# STM32F405RGT6.net
KiCad netlist of a schematic drawn in Altium Designer
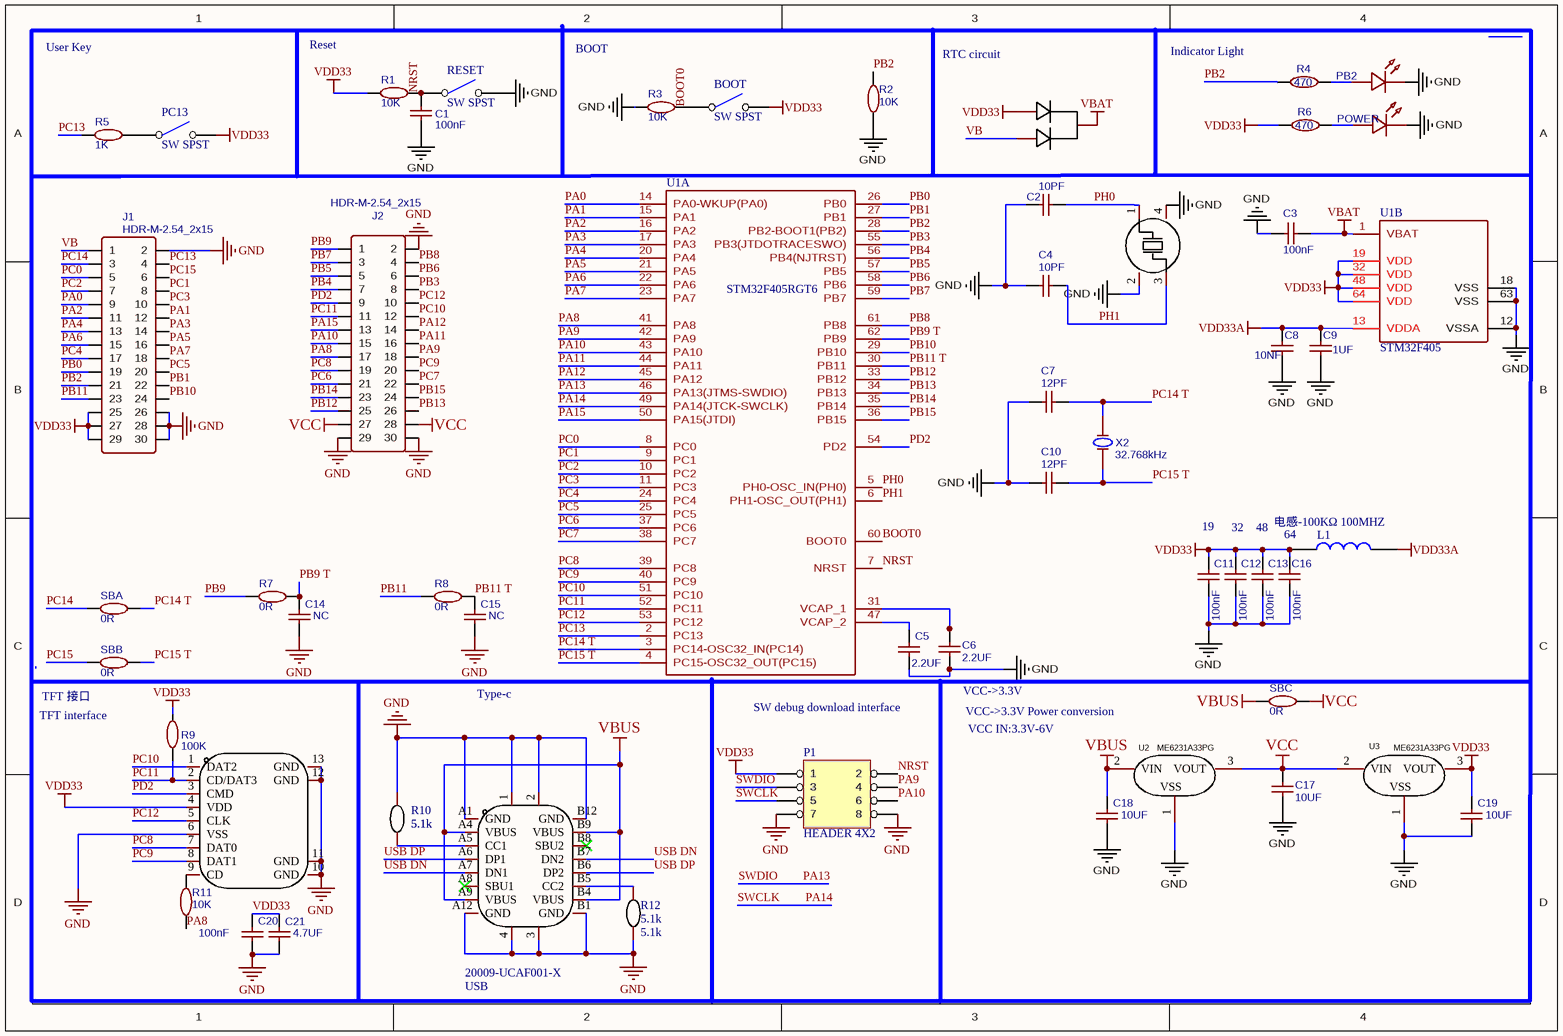
[diagram p0: STM32F405RGT6 .schdoc]

(export (version "E")
  (design (tool "Eeschema 10.0.6"))
  (components
    (comp (ref "BOOT") (value "SW SPST") (footprint "KEY-SMD1") (libsource (lib "杂元件库") (part "SW SPST")))
    (comp (ref "C1")
      (value "100nF")
      (footprint "C0603")
      (fields (field (name "MANUFACTURER") "FH") (field (name "MANUFACTURER PART") "0603B104K500NT"))
      (libsource (lib "altium-import") (part "root_1_100nF_"))
    )
    (comp (ref "C2")
      (value "10PF")
      (footprint "C0603")
      (fields (field (name "MANUFACTURER") "YAGEO") (field (name "MANUFACTURER PART") "CC0603JRNPO9BN200"))
      (libsource (lib "altium-import") (part "root_0_20pF_"))
    )
    (comp (ref "C3")
      (value "100nF")
      (footprint "C0603")
      (fields (field (name "MANUFACTURER") "FH") (field (name "MANUFACTURER PART") "0603B104K500NT"))
      (libsource (lib "altium-import") (part "root_2_100nF_"))
    )
    (comp (ref "C4")
      (value "10PF")
      (footprint "C0603")
      (fields (field (name "MANUFACTURER") "YAGEO") (field (name "MANUFACTURER PART") "CC0603JRNPO9BN200"))
      (libsource (lib "altium-import") (part "root_0_20pF_"))
    )
    (comp (ref "C5")
      (value "2.2UF")
      (footprint "C0603")
      (fields (field (name "MANUFACTURER") "FH") (field (name "MANUFACTURER PART") "0603B104K500NT"))
      (libsource (lib "altium-import") (part "root_1_100nF_"))
    )
    (comp (ref "C6")
      (value "2.2UF")
      (footprint "C0603")
      (fields (field (name "MANUFACTURER") "FH") (field (name "MANUFACTURER PART") "0603B104K500NT"))
      (libsource (lib "altium-import") (part "root_1_100nF_"))
    )
    (comp (ref "C7")
      (value "12PF")
      (footprint "C0603")
      (fields (field (name "MANUFACTURER") "YAGEO") (field (name "MANUFACTURER PART") "CC0603JRNPO9BN200"))
      (libsource (lib "altium-import") (part "root_0_20pF_"))
    )
    (comp (ref "C8")
      (value "10NF")
      (footprint "C0603")
      (fields (field (name "MANUFACTURER") "FH") (field (name "MANUFACTURER PART") "0603B104K500NT"))
      (libsource (lib "altium-import") (part "root_1_100nF_"))
    )
    (comp (ref "C9")
      (value "1UF")
      (footprint "C0603")
      (fields (field (name "MANUFACTURER") "FH") (field (name "MANUFACTURER PART") "0603B104K500NT"))
      (libsource (lib "altium-import") (part "root_1_100nF_"))
    )
    (comp (ref "C10")
      (value "12PF")
      (footprint "C0603")
      (fields (field (name "MANUFACTURER") "YAGEO") (field (name "MANUFACTURER PART") "CC0603JRNPO9BN200"))
      (libsource (lib "altium-import") (part "root_0_20pF_"))
    )
    (comp (ref "C11")
      (value "100nF")
      (footprint "C0603")
      (fields (field (name "MANUFACTURER") "FH") (field (name "MANUFACTURER PART") "0603B104K500NT"))
      (libsource (lib "altium-import") (part "root_1_100nF_"))
    )
    (comp (ref "C12")
      (value "100nF")
      (footprint "C0603")
      (fields (field (name "MANUFACTURER") "FH") (field (name "MANUFACTURER PART") "0603B104K500NT"))
      (libsource (lib "altium-import") (part "root_1_100nF_"))
    )
    (comp (ref "C13")
      (value "100nF")
      (footprint "C0603")
      (fields (field (name "MANUFACTURER") "FH") (field (name "MANUFACTURER PART") "0603B104K500NT"))
      (libsource (lib "altium-import") (part "root_1_100nF_"))
    )
    (comp (ref "C14")
      (value "NC")
      (footprint "C0603")
      (fields (field (name "MANUFACTURER") "FH") (field (name "MANUFACTURER PART") "0603B104K500NT"))
      (libsource (lib "altium-import") (part "root_1_100nF_"))
    )
    (comp (ref "C15")
      (value "NC")
      (footprint "C0603")
      (fields (field (name "MANUFACTURER") "FH") (field (name "MANUFACTURER PART") "0603B104K500NT"))
      (libsource (lib "altium-import") (part "root_1_100nF_"))
    )
    (comp (ref "C16")
      (value "100nF")
      (footprint "C0603")
      (fields (field (name "MANUFACTURER") "FH") (field (name "MANUFACTURER PART") "0603B104K500NT"))
      (libsource (lib "altium-import") (part "root_1_100nF_"))
    )
    (comp (ref "C17")
      (value "10UF")
      (footprint "C0603")
      (fields (field (name "MANUFACTURER") "FH") (field (name "MANUFACTURER PART") "0603B104K500NT"))
      (libsource (lib "altium-import") (part "root_3_100nF_"))
    )
    (comp (ref "C18")
      (value "10UF")
      (footprint "C0603")
      (fields (field (name "MANUFACTURER") "FH") (field (name "MANUFACTURER PART") "0603B104K500NT"))
      (libsource (lib "altium-import") (part "root_1_100nF_"))
    )
    (comp (ref "C19")
      (value "10UF")
      (footprint "C0603")
      (fields (field (name "MANUFACTURER") "FH") (field (name "MANUFACTURER PART") "0603B104K500NT"))
      (libsource (lib "altium-import") (part "root_1_100nF_"))
    )
    (comp (ref "C20")
      (value "100nF")
      (footprint "C0603")
      (fields (field (name "MANUFACTURER") "FH") (field (name "MANUFACTURER PART") "0603B104K500NT"))
      (libsource (lib "altium-import") (part "root_1_100nF_"))
    )
    (comp (ref "C21")
      (value "4.7UF")
      (footprint "C0603")
      (fields (field (name "MANUFACTURER") "FH") (field (name "MANUFACTURER PART") "0603B104K500NT"))
      (libsource (lib "altium-import") (part "root_1_100nF_"))
    )
    (comp (ref "CARD1")
      (value "TF-01A")
      (footprint "SD -TF-01A")
      (fields (field (name "MANUFACTURER") "Yuandi(元迪)"))
      (libsource (lib "altium-import") (part "root_0_TF-01A_C2889258_"))
    )
    (comp (ref "D1")
      (value "BAT54C")
      (footprint "SOT-23")
      (fields (field (name "MANUFACTURER") "CJ(江苏长电/长晶)"))
      (libsource (lib "altium-import") (part "root_0_BAT54C_C2135_"))
    )
    (comp (ref "J1")
      (value "HDR-M-2.54_2x15")
      (footprint "HDR2X15-")
      (fields (field (name "CONTRIBUTOR") "LCEDA_Lib"))
      (libsource (lib "altium-import") (part "root_0_HDR-M-2.54_2x15_"))
    )
    (comp (ref "J2")
      (value "HDR-M-2.54_2x15")
      (footprint "HDR2X15-")
      (fields (field (name "CONTRIBUTOR") "LCEDA_Lib"))
      (libsource (lib "altium-import") (part "root_0_HDR-M-2.54_2x15_"))
    )
    (comp (ref "L1") (value "电感-100KΩ 100MHZ") (footprint "L0603") (libsource (lib "杂元件库") (part "电感")))
    (comp (ref "P1")
      (value "HEADER 4X2")
      (footprint "HDR2X4H-OK")
      (libsource (lib "杂元件库") (part "HEADER 4X2"))
    )
    (comp (ref "PB2")
      (value "LED-0603_G")
      (footprint "LED0603-G")
      (fields
        (field (name "MANUFACTURER") "EVERLIGHT(台湾亿光)")
        (field (name "MANUFACTURER PART") "19-217/R6C-AL1M2VY/3T")
        (field (name "CONTRIBUTOR") "LCEDA_01")
      )
      (libsource (lib "altium-import") (part "root_0_LED-0603_R_"))
    )
    (comp (ref "PC13") (value "SW SPST") (footprint "KEY-SMD1") (libsource (lib "杂元件库") (part "SW SPST")))
    (comp (ref "POWER")
      (value "LED-0603_R")
      (footprint "LED0603-R")
      (fields
        (field (name "MANUFACTURER") "EVERLIGHT(台湾亿光)")
        (field (name "MANUFACTURER PART") "19-217/R6C-AL1M2VY/3T")
        (field (name "CONTRIBUTOR") "LCEDA_01")
      )
      (libsource (lib "altium-import") (part "root_0_LED-0603_R_"))
    )
    (comp (ref "R1")
      (value "10K")
      (footprint "R0603")
      (fields (field (name "MANUFACTURER") "YAGEO") (field (name "MANUFACTURER PART") "RC0603FR-0710KL"))
      (libsource (lib "altium-import") (part "root_2_10K_"))
    )
    (comp (ref "R2")
      (value "10K")
      (footprint "R0603")
      (fields (field (name "MANUFACTURER") "YAGEO") (field (name "MANUFACTURER PART") "RC0603FR-0710KL"))
      (libsource (lib "altium-import") (part "root_3_10K_"))
    )
    (comp (ref "R3")
      (value "10K")
      (footprint "R0603")
      (fields (field (name "MANUFACTURER") "YAGEO") (field (name "MANUFACTURER PART") "RC0603FR-0710KL"))
      (libsource (lib "altium-import") (part "root_2_10K_"))
    )
    (comp (ref "R4")
      (value "470")
      (footprint "R0603")
      (fields (field (name "MANUFACTURER") "UniOhm") (field (name "MANUFACTURER PART") "0603WAJ0471T5E"))
      (libsource (lib "altium-import") (part "root_0_470_"))
    )
    (comp (ref "R5")
      (value "1K")
      (footprint "R0603")
      (fields (field (name "MANUFACTURER") "YAGEO") (field (name "MANUFACTURER PART") "RC0603FR-0710KL"))
      (libsource (lib "altium-import") (part "root_2_10K_"))
    )
    (comp (ref "R6")
      (value "470")
      (footprint "R0603")
      (fields (field (name "MANUFACTURER") "UniOhm") (field (name "MANUFACTURER PART") "0603WAJ0471T5E"))
      (libsource (lib "altium-import") (part "root_0_470_"))
    )
    (comp (ref "R7")
      (value "0R")
      (footprint "R0603")
      (fields (field (name "MANUFACTURER") "YAGEO") (field (name "MANUFACTURER PART") "RC0603FR-0710KL"))
      (libsource (lib "altium-import") (part "root_2_10K_"))
    )
    (comp (ref "R8")
      (value "0R")
      (footprint "R0603")
      (fields (field (name "MANUFACTURER") "YAGEO") (field (name "MANUFACTURER PART") "RC0603FR-0710KL"))
      (libsource (lib "altium-import") (part "root_2_10K_"))
    )
    (comp (ref "R9")
      (value "100K")
      (footprint "R0603")
      (fields (field (name "MANUFACTURER") "YAGEO") (field (name "MANUFACTURER PART") "RC0603FR-0710KL"))
      (libsource (lib "altium-import") (part "root_1_10K_"))
    )
    (comp (ref "R10")
      (value "5.1k")
      (footprint "R0603")
      (fields (field (name "NAME") "5.1k"))
      (libsource (lib "altium-import") (part "root_1_5.1k_"))
    )
    (comp (ref "R11")
      (value "10K")
      (footprint "R0603")
      (fields (field (name "MANUFACTURER") "YAGEO") (field (name "MANUFACTURER PART") "RC0603FR-0710KL"))
      (libsource (lib "altium-import") (part "root_3_10K_"))
    )
    (comp (ref "R12")
      (value "5.1k")
      (footprint "R0603")
      (fields (field (name "NAME") "5.1k"))
      (libsource (lib "altium-import") (part "root_3_5.1k_"))
    )
    (comp (ref "RESET") (value "SW SPST") (footprint "KEY-SMD1") (libsource (lib "杂元件库") (part "SW SPST")))
    (comp (ref "SBA")
      (value "0R")
      (footprint "R0805")
      (fields (field (name "MANUFACTURER") "YAGEO") (field (name "MANUFACTURER PART") "RC0603FR-0710KL"))
      (libsource (lib "altium-import") (part "root_2_10K_"))
    )
    (comp (ref "SBB")
      (value "0R")
      (footprint "R0805")
      (fields (field (name "MANUFACTURER") "YAGEO") (field (name "MANUFACTURER PART") "RC0603FR-0710KL"))
      (libsource (lib "altium-import") (part "root_2_10K_"))
    )
    (comp (ref "SBC")
      (value "0R")
      (footprint "R0805")
      (fields (field (name "MANUFACTURER") "YAGEO") (field (name "MANUFACTURER PART") "RC0603FR-0710KL"))
      (libsource (lib "altium-import") (part "root_2_10K_"))
    )
    (comp (ref "U1") (value "STM32F405RGT6") (footprint "QFP-64") (libsource (lib "杂元件库") (part "STM32F405")))
    (comp (ref "U2")
      (value "ME6231A33PG")
      (footprint "SOT-89")
      (fields (field (name "MANUFACTURER") "MICRONE(南京微盟)"))
      (libsource (lib "altium-import") (part "root_0_ME6231A33PG_"))
    )
    (comp (ref "U3")
      (value "ME6231A33PG")
      (footprint "SOT-89")
      (fields (field (name "MANUFACTURER") "MICRONE(南京微盟)"))
      (libsource (lib "altium-import") (part "root_0_ME6231A33PG_"))
    )
    (comp (ref "USB")
      (value "20009-UCAF001-X")
      (footprint "TYPE-C-16P")
      (fields (field (name "NAME") "20009-UCAF001-X") (field (name "MANUFACTURER") "MINTRON(��˶)"))
      (libsource (lib "altium-import") (part "root_0_20009-UCAF001-X_"))
    )
    (comp (ref "X1")
      (value "8MHz")
      (footprint "3225晶振")
      (description "C20617566")
      (fields (field (name "MANUFACTURER") "YXC(扬兴晶振)") (field (name "MANUFACTURER PART") "X322525MOB4SI"))
      (libsource (lib "altium-import") (part "root_3_X322525MOB4SI_"))
    )
    (comp (ref "X2")
      (value "32.768kHz")
      (footprint "3215")
      (fields (field (name "MANUFACTURER PART") "X308032768KGB2SC") (field (name "MANUFACTURER") "YXC(扬兴晶振)"))
      (libsource (lib "altium-import") (part "root_1_32.768kHz_"))
    )
  )
  (nets
    (net (code "1") (name "/BOOT0") (class "Default")
      (node (ref "BOOT") (pin "1") (pinfunction "COMMON_1") (pintype "passive"))
      (node (ref "R3") (pin "1") (pinfunction "1_1") (pintype "passive"))
      (node (ref "U1") (pin "60") (pinfunction "BOOT0_60") (pintype "passive"))
    )
    (net (code "2") (name "/NRST") (class "Default")
      (node (ref "C1") (pin "2") (pinfunction "2_2") (pintype "passive"))
      (node (ref "P1") (pin "2") (pinfunction "2_2") (pintype "passive"))
      (node (ref "R1") (pin "1") (pinfunction "1_1") (pintype "passive"))
      (node (ref "RESET") (pin "1") (pinfunction "COMMON_1") (pintype "passive"))
      (node (ref "U1") (pin "7") (pinfunction "NRST_7") (pintype "passive"))
    )
    (net (code "3") (name "/PA0") (class "Default")
      (node (ref "J1") (pin "9") (pinfunction "9_9") (pintype "passive"))
      (node (ref "U1") (pin "14") (pinfunction "PA0-WKUP(PA0)_14") (pintype "passive"))
    )
    (net (code "4") (name "/PA1") (class "Default")
      (node (ref "J1") (pin "12") (pinfunction "12_12") (pintype "passive"))
      (node (ref "U1") (pin "15") (pinfunction "PA1_15") (pintype "passive"))
    )
    (net (code "5") (name "/PA2") (class "Default")
      (node (ref "J1") (pin "11") (pinfunction "11_11") (pintype "passive"))
      (node (ref "U1") (pin "16") (pinfunction "PA2_16") (pintype "passive"))
    )
    (net (code "6") (name "/PA3") (class "Default")
      (node (ref "J1") (pin "14") (pinfunction "14_14") (pintype "passive"))
      (node (ref "U1") (pin "17") (pinfunction "PA3_17") (pintype "passive"))
    )
    (net (code "7") (name "/PA4") (class "Default")
      (node (ref "J1") (pin "13") (pinfunction "13_13") (pintype "passive"))
      (node (ref "U1") (pin "20") (pinfunction "PA4_20") (pintype "passive"))
    )
    (net (code "8") (name "/PA5") (class "Default")
      (node (ref "J1") (pin "16") (pinfunction "16_16") (pintype "passive"))
      (node (ref "U1") (pin "21") (pinfunction "PA5_21") (pintype "passive"))
    )
    (net (code "9") (name "/PA6") (class "Default")
      (node (ref "J1") (pin "15") (pinfunction "15_15") (pintype "passive"))
      (node (ref "U1") (pin "22") (pinfunction "PA6_22") (pintype "passive"))
    )
    (net (code "10") (name "/PA7") (class "Default")
      (node (ref "J1") (pin "18") (pinfunction "18_18") (pintype "passive"))
      (node (ref "U1") (pin "23") (pinfunction "PA7_23") (pintype "passive"))
    )
    (net (code "11") (name "/PA8") (class "Default")
      (node (ref "J2") (pin "17") (pinfunction "17_17") (pintype "passive"))
      (node (ref "R11") (pin "2") (pinfunction "2_2") (pintype "passive"))
      (node (ref "U1") (pin "41") (pinfunction "PA8_41") (pintype "passive"))
    )
    (net (code "12") (name "/PA9") (class "Default")
      (node (ref "J2") (pin "18") (pinfunction "18_18") (pintype "passive"))
      (node (ref "P1") (pin "4") (pinfunction "4_4") (pintype "passive"))
      (node (ref "U1") (pin "42") (pinfunction "PA9_42") (pintype "passive"))
    )
    (net (code "13") (name "/PA10") (class "Default")
      (node (ref "J2") (pin "15") (pinfunction "15_15") (pintype "passive"))
      (node (ref "P1") (pin "6") (pinfunction "6_6") (pintype "passive"))
      (node (ref "U1") (pin "43") (pinfunction "PA10_43") (pintype "passive"))
    )
    (net (code "14") (name "/PA11") (class "Default")
      (node (ref "J2") (pin "16") (pinfunction "16_16") (pintype "passive"))
      (node (ref "U1") (pin "44") (pinfunction "PA11_44") (pintype "passive"))
    )
    (net (code "15") (name "/PA12") (class "Default")
      (node (ref "J2") (pin "14") (pinfunction "14_14") (pintype "passive"))
      (node (ref "U1") (pin "45") (pinfunction "PA12_45") (pintype "passive"))
    )
    (net (code "16") (name "/PA13") (class "Default")
      (node (ref "P1") (pin "3") (pinfunction "3_3") (pintype "passive"))
      (node (ref "U1") (pin "46") (pinfunction "PA13(JTMS-SWDIO)_46") (pintype "passive"))
    )
    (net (code "17") (name "/PA14") (class "Default")
      (node (ref "P1") (pin "5") (pinfunction "5_5") (pintype "passive"))
      (node (ref "U1") (pin "49") (pinfunction "PA14(JTCK-SWCLK)_49") (pintype "passive"))
    )
    (net (code "18") (name "/PA15") (class "Default")
      (node (ref "J2") (pin "13") (pinfunction "13_13") (pintype "passive"))
      (node (ref "U1") (pin "50") (pinfunction "PA15(JTDI)_50") (pintype "passive"))
    )
    (net (code "19") (name "/PB0") (class "Default")
      (node (ref "J1") (pin "19") (pinfunction "19_19") (pintype "passive"))
      (node (ref "U1") (pin "26") (pinfunction "PB0_26") (pintype "passive"))
    )
    (net (code "20") (name "/PB1") (class "Default")
      (node (ref "J1") (pin "22") (pinfunction "22_22") (pintype "passive"))
      (node (ref "U1") (pin "27") (pinfunction "PB1_27") (pintype "passive"))
    )
    (net (code "21") (name "/PB2") (class "Default")
      (node (ref "J1") (pin "21") (pinfunction "21_21") (pintype "passive"))
      (node (ref "R2") (pin "1") (pinfunction "1_1") (pintype "passive"))
      (node (ref "R4") (pin "1") (pinfunction "1_1") (pintype "passive"))
      (node (ref "U1") (pin "28") (pinfunction "PB2-BOOT1(PB2)_28") (pintype "passive"))
    )
    (net (code "22") (name "/PB3") (class "Default")
      (node (ref "J2") (pin "8") (pinfunction "8_8") (pintype "passive"))
      (node (ref "U1") (pin "55") (pinfunction "PB3(JTDOTRACESWO)_55") (pintype "passive"))
    )
    (net (code "23") (name "/PB4") (class "Default")
      (node (ref "J2") (pin "7") (pinfunction "7_7") (pintype "passive"))
      (node (ref "U1") (pin "56") (pinfunction "PB4(NJTRST)_56") (pintype "passive"))
    )
    (net (code "24") (name "/PB5") (class "Default")
      (node (ref "J2") (pin "5") (pinfunction "5_5") (pintype "passive"))
      (node (ref "U1") (pin "57") (pinfunction "PB5_57") (pintype "passive"))
    )
    (net (code "25") (name "/PB6") (class "Default")
      (node (ref "J2") (pin "6") (pinfunction "6_6") (pintype "passive"))
      (node (ref "U1") (pin "58") (pinfunction "PB6_58") (pintype "passive"))
    )
    (net (code "26") (name "/PB7") (class "Default")
      (node (ref "J2") (pin "3") (pinfunction "3_3") (pintype "passive"))
      (node (ref "U1") (pin "59") (pinfunction "PB7_59") (pintype "passive"))
    )
    (net (code "27") (name "/PB8") (class "Default")
      (node (ref "J2") (pin "4") (pinfunction "4_4") (pintype "passive"))
      (node (ref "U1") (pin "61") (pinfunction "PB8_61") (pintype "passive"))
    )
    (net (code "28") (name "/PB9") (class "Default")
      (node (ref "J2") (pin "1") (pinfunction "1_1") (pintype "passive"))
      (node (ref "R7") (pin "2") (pinfunction "2_2") (pintype "passive"))
    )
    (net (code "29") (name "/PB9 T") (class "Default")
      (node (ref "C14") (pin "2") (pinfunction "2_2") (pintype "passive"))
      (node (ref "R7") (pin "1") (pinfunction "1_1") (pintype "passive"))
      (node (ref "U1") (pin "62") (pinfunction "PB9_62") (pintype "passive"))
    )
    (net (code "30") (name "/PB10") (class "Default")
      (node (ref "J1") (pin "24") (pinfunction "24_24") (pintype "passive"))
      (node (ref "U1") (pin "29") (pinfunction "PB10_29") (pintype "passive"))
    )
    (net (code "31") (name "/PB11") (class "Default")
      (node (ref "J1") (pin "23") (pinfunction "23_23") (pintype "passive"))
      (node (ref "R8") (pin "2") (pinfunction "2_2") (pintype "passive"))
    )
    (net (code "32") (name "/PB11 T") (class "Default")
      (node (ref "C15") (pin "2") (pinfunction "2_2") (pintype "passive"))
      (node (ref "R8") (pin "1") (pinfunction "1_1") (pintype "passive"))
      (node (ref "U1") (pin "30") (pinfunction "PB11_30") (pintype "passive"))
    )
    (net (code "33") (name "/PB12") (class "Default")
      (node (ref "J2") (pin "25") (pinfunction "25_25") (pintype "passive"))
      (node (ref "U1") (pin "33") (pinfunction "PB12_33") (pintype "passive"))
    )
    (net (code "34") (name "/PB13") (class "Default")
      (node (ref "J2") (pin "26") (pinfunction "26_26") (pintype "passive"))
      (node (ref "U1") (pin "34") (pinfunction "PB13_34") (pintype "passive"))
    )
    (net (code "35") (name "/PB14") (class "Default")
      (node (ref "J2") (pin "23") (pinfunction "23_23") (pintype "passive"))
      (node (ref "U1") (pin "35") (pinfunction "PB14_35") (pintype "passive"))
    )
    (net (code "36") (name "/PB15") (class "Default")
      (node (ref "J2") (pin "24") (pinfunction "24_24") (pintype "passive"))
      (node (ref "U1") (pin "36") (pinfunction "PB15_36") (pintype "passive"))
    )
    (net (code "37") (name "/PC0") (class "Default")
      (node (ref "J1") (pin "5") (pinfunction "5_5") (pintype "passive"))
      (node (ref "U1") (pin "8") (pinfunction "PC0_8") (pintype "passive"))
    )
    (net (code "38") (name "/PC1") (class "Default")
      (node (ref "J1") (pin "8") (pinfunction "8_8") (pintype "passive"))
      (node (ref "U1") (pin "9") (pinfunction "PC1_9") (pintype "passive"))
    )
    (net (code "39") (name "/PC2") (class "Default")
      (node (ref "J1") (pin "7") (pinfunction "7_7") (pintype "passive"))
      (node (ref "U1") (pin "10") (pinfunction "PC2_10") (pintype "passive"))
    )
    (net (code "40") (name "/PC3") (class "Default")
      (node (ref "J1") (pin "10") (pinfunction "10_10") (pintype "passive"))
      (node (ref "U1") (pin "11") (pinfunction "PC3_11") (pintype "passive"))
    )
    (net (code "41") (name "/PC4") (class "Default")
      (node (ref "J1") (pin "17") (pinfunction "17_17") (pintype "passive"))
      (node (ref "U1") (pin "24") (pinfunction "PC4_24") (pintype "passive"))
    )
    (net (code "42") (name "/PC5") (class "Default")
      (node (ref "J1") (pin "20") (pinfunction "20_20") (pintype "passive"))
      (node (ref "U1") (pin "25") (pinfunction "PC5_25") (pintype "passive"))
    )
    (net (code "43") (name "/PC6") (class "Default")
      (node (ref "J2") (pin "21") (pinfunction "21_21") (pintype "passive"))
      (node (ref "U1") (pin "37") (pinfunction "PC6_37") (pintype "passive"))
    )
    (net (code "44") (name "/PC7") (class "Default")
      (node (ref "J2") (pin "22") (pinfunction "22_22") (pintype "passive"))
      (node (ref "U1") (pin "38") (pinfunction "PC7_38") (pintype "passive"))
    )
    (net (code "45") (name "/PC8") (class "Default")
      (node (ref "CARD1") (pin "7") (pinfunction "DAT0_7") (pintype "passive"))
      (node (ref "J2") (pin "19") (pinfunction "19_19") (pintype "passive"))
      (node (ref "U1") (pin "39") (pinfunction "PC8_39") (pintype "passive"))
    )
    (net (code "46") (name "/PC9") (class "Default")
      (node (ref "CARD1") (pin "8") (pinfunction "DAT1_8") (pintype "passive"))
      (node (ref "J2") (pin "20") (pinfunction "20_20") (pintype "passive"))
      (node (ref "U1") (pin "40") (pinfunction "PC9_40") (pintype "passive"))
    )
    (net (code "47") (name "/PC10") (class "Default")
      (node (ref "CARD1") (pin "1") (pinfunction "DAT2_1") (pintype "passive"))
      (node (ref "J2") (pin "12") (pinfunction "12_12") (pintype "passive"))
      (node (ref "U1") (pin "51") (pinfunction "PC10_51") (pintype "passive"))
    )
    (net (code "48") (name "/PC11") (class "Default")
      (node (ref "CARD1") (pin "2") (pinfunction "CD/DAT3_2") (pintype "passive"))
      (node (ref "J2") (pin "11") (pinfunction "11_11") (pintype "passive"))
      (node (ref "R9") (pin "1") (pinfunction "1_1") (pintype "passive"))
      (node (ref "U1") (pin "52") (pinfunction "PC11_52") (pintype "passive"))
    )
    (net (code "49") (name "/PC12") (class "Default")
      (node (ref "CARD1") (pin "5") (pinfunction "CLK_5") (pintype "passive"))
      (node (ref "J2") (pin "10") (pinfunction "10_10") (pintype "passive"))
      (node (ref "U1") (pin "53") (pinfunction "PC12_53") (pintype "passive"))
    )
    (net (code "50") (name "/PC13") (class "Default")
      (node (ref "J1") (pin "4") (pinfunction "4_4") (pintype "passive"))
      (node (ref "R5") (pin "2") (pinfunction "2_2") (pintype "passive"))
      (node (ref "U1") (pin "2") (pinfunction "PC13_2") (pintype "passive"))
    )
    (net (code "51") (name "/PC14") (class "Default")
      (node (ref "J1") (pin "3") (pinfunction "3_3") (pintype "passive"))
      (node (ref "SBA") (pin "2") (pinfunction "2_2") (pintype "passive"))
    )
    (net (code "52") (name "/PC14 T") (class "Default")
      (node (ref "C7") (pin "2") (pinfunction "2_2") (pintype "passive"))
      (node (ref "SBA") (pin "1") (pinfunction "1_1") (pintype "passive"))
      (node (ref "U1") (pin "3") (pinfunction "PC14-OSC32_IN(PC14)_3") (pintype "passive"))
      (node (ref "X2") (pin "2") (pinfunction "OSC2_2") (pintype "passive"))
    )
    (net (code "53") (name "/PC15") (class "Default")
      (node (ref "J1") (pin "6") (pinfunction "6_6") (pintype "passive"))
      (node (ref "SBB") (pin "2") (pinfunction "2_2") (pintype "passive"))
    )
    (net (code "54") (name "/PC15 T") (class "Default")
      (node (ref "C10") (pin "2") (pinfunction "2_2") (pintype "passive"))
      (node (ref "SBB") (pin "1") (pinfunction "1_1") (pintype "passive"))
      (node (ref "U1") (pin "4") (pinfunction "PC15-OSC32_OUT(PC15)_4") (pintype "passive"))
      (node (ref "X2") (pin "1") (pinfunction "OSC1_1") (pintype "passive"))
    )
    (net (code "55") (name "/PD2") (class "Default")
      (node (ref "CARD1") (pin "3") (pinfunction "CMD_3") (pintype "passive"))
      (node (ref "J2") (pin "9") (pinfunction "9_9") (pintype "passive"))
      (node (ref "U1") (pin "54") (pinfunction "PD2_54") (pintype "passive"))
    )
    (net (code "56") (name "/PH0") (class "Default")
      (node (ref "C2") (pin "2") (pinfunction "2_2") (pintype "passive"))
      (node (ref "U1") (pin "5") (pinfunction "PH0-OSC_IN(PH0)_5") (pintype "passive"))
      (node (ref "X1") (pin "1") (pinfunction "OSC1_1") (pintype "passive"))
    )
    (net (code "57") (name "/PH1") (class "Default")
      (node (ref "C4") (pin "2") (pinfunction "2_2") (pintype "passive"))
      (node (ref "U1") (pin "6") (pinfunction "PH1-OSC_OUT(PH1)_6") (pintype "passive"))
      (node (ref "X1") (pin "3") (pinfunction "OSC2_3") (pintype "passive"))
    )
    (net (code "58") (name "/USB DN") (class "Default")
      (node (ref "USB") (pin "A7") (pinfunction "DN1_A7") (pintype "passive"))
      (node (ref "USB") (pin "B7") (pinfunction "DN2_B7") (pintype "passive"))
    )
    (net (code "59") (name "/USB DP") (class "Default")
      (node (ref "USB") (pin "A6") (pinfunction "DP1_A6") (pintype "passive"))
      (node (ref "USB") (pin "B6") (pinfunction "DP2_B6") (pintype "passive"))
    )
    (net (code "60") (name "/VB") (class "Default")
      (node (ref "D1") (pin "2") (pinfunction "A2_2") (pintype "passive"))
      (node (ref "J1") (pin "1") (pinfunction "1_1") (pintype "passive"))
    )
    (net (code "61") (name "GND") (class "Default")
      (node (ref "C1") (pin "1") (pinfunction "1_1") (pintype "passive"))
      (node (ref "C10") (pin "1") (pinfunction "1_1") (pintype "passive"))
      (node (ref "C11") (pin "1") (pinfunction "1_1") (pintype "passive"))
      (node (ref "C12") (pin "1") (pinfunction "1_1") (pintype "passive"))
      (node (ref "C13") (pin "1") (pinfunction "1_1") (pintype "passive"))
      (node (ref "C14") (pin "1") (pinfunction "1_1") (pintype "passive"))
      (node (ref "C15") (pin "1") (pinfunction "1_1") (pintype "passive"))
      (node (ref "C16") (pin "1") (pinfunction "1_1") (pintype "passive"))
      (node (ref "C17") (pin "2") (pinfunction "2_2") (pintype "passive"))
      (node (ref "C18") (pin "1") (pinfunction "1_1") (pintype "passive"))
      (node (ref "C19") (pin "1") (pinfunction "1_1") (pintype "passive"))
      (node (ref "C2") (pin "1") (pinfunction "1_1") (pintype "passive"))
      (node (ref "C20") (pin "1") (pinfunction "1_1") (pintype "passive"))
      (node (ref "C21") (pin "1") (pinfunction "1_1") (pintype "passive"))
      (node (ref "C3") (pin "2") (pinfunction "2_2") (pintype "passive"))
      (node (ref "C4") (pin "1") (pinfunction "1_1") (pintype "passive"))
      (node (ref "C5") (pin "1") (pinfunction "1_1") (pintype "passive"))
      (node (ref "C6") (pin "1") (pinfunction "1_1") (pintype "passive"))
      (node (ref "C7") (pin "1") (pinfunction "1_1") (pintype "passive"))
      (node (ref "C8") (pin "1") (pinfunction "1_1") (pintype "passive"))
      (node (ref "C9") (pin "1") (pinfunction "1_1") (pintype "passive"))
      (node (ref "CARD1") (pin "10") (pinfunction "GND_10") (pintype "passive"))
      (node (ref "CARD1") (pin "11") (pinfunction "GND_11") (pintype "passive"))
      (node (ref "CARD1") (pin "12") (pinfunction "GND_12") (pintype "passive"))
      (node (ref "CARD1") (pin "13") (pinfunction "GND_13") (pintype "passive"))
      (node (ref "CARD1") (pin "6") (pinfunction "VSS_6") (pintype "passive"))
      (node (ref "J1") (pin "2") (pinfunction "2_2") (pintype "passive"))
      (node (ref "J1") (pin "26") (pinfunction "26_26") (pintype "passive"))
      (node (ref "J1") (pin "28") (pinfunction "28_28") (pintype "passive"))
      (node (ref "J1") (pin "30") (pinfunction "30_30") (pintype "passive"))
      (node (ref "J2") (pin "2") (pinfunction "2_2") (pintype "passive"))
      (node (ref "J2") (pin "29") (pinfunction "29_29") (pintype "passive"))
      (node (ref "J2") (pin "30") (pinfunction "30_30") (pintype "passive"))
      (node (ref "P1") (pin "7") (pinfunction "7_7") (pintype "passive"))
      (node (ref "P1") (pin "8") (pinfunction "8_8") (pintype "passive"))
      (node (ref "PB2") (pin "2") (pinfunction "2_2") (pintype "passive"))
      (node (ref "POWER") (pin "2") (pinfunction "2_2") (pintype "passive"))
      (node (ref "R10") (pin "2") (pinfunction "2_2") (pintype "passive"))
      (node (ref "R12") (pin "2") (pinfunction "2_2") (pintype "passive"))
      (node (ref "R2") (pin "2") (pinfunction "2_2") (pintype "passive"))
      (node (ref "R3") (pin "2") (pinfunction "2_2") (pintype "passive"))
      (node (ref "RESET") (pin "2") (pinfunction "NO_2") (pintype "passive"))
      (node (ref "U1") (pin "12") (pinfunction "VSSA_12") (pintype "passive"))
      (node (ref "U1") (pin "18") (pinfunction "VSS_18") (pintype "passive"))
      (node (ref "U1") (pin "63") (pinfunction "VSS_63") (pintype "passive"))
      (node (ref "U2") (pin "1") (pinfunction "VSS_1") (pintype "passive"))
      (node (ref "U3") (pin "1") (pinfunction "VSS_1") (pintype "passive"))
      (node (ref "USB") (pin "1") (pinfunction "1_1") (pintype "passive"))
      (node (ref "USB") (pin "2") (pinfunction "2_2") (pintype "passive"))
      (node (ref "USB") (pin "3") (pinfunction "3_3") (pintype "passive"))
      (node (ref "USB") (pin "4") (pinfunction "4_4") (pintype "passive"))
      (node (ref "USB") (pin "A1") (pinfunction "GND_A1") (pintype "passive"))
      (node (ref "USB") (pin "A12") (pinfunction "GND_A12") (pintype "passive"))
      (node (ref "USB") (pin "B1") (pinfunction "GND_B1") (pintype "passive"))
      (node (ref "USB") (pin "B12") (pinfunction "GND_B12") (pintype "passive"))
      (node (ref "X1") (pin "2") (pinfunction "GND_2") (pintype "passive"))
      (node (ref "X1") (pin "4") (pinfunction "GND_4") (pintype "passive"))
    )
    (net (code "62") (name "Net-(CARD1-CD)") (class "Default")
      (node (ref "CARD1") (pin "9") (pinfunction "CD_9") (pintype "passive"))
      (node (ref "R11") (pin "1") (pinfunction "1_1") (pintype "passive"))
    )
    (net (code "63") (name "Net-(PB2-Pad1)") (class "Default")
      (node (ref "PB2") (pin "1") (pinfunction "1_1") (pintype "passive"))
      (node (ref "R4") (pin "2") (pinfunction "2_2") (pintype "passive"))
    )
    (net (code "64") (name "Net-(PC13-COMMON)") (class "Default")
      (node (ref "PC13") (pin "1") (pinfunction "COMMON_1") (pintype "passive"))
      (node (ref "R5") (pin "1") (pinfunction "1_1") (pintype "passive"))
    )
    (net (code "65") (name "Net-(POWER-Pad1)") (class "Default")
      (node (ref "POWER") (pin "1") (pinfunction "1_1") (pintype "passive"))
      (node (ref "R6") (pin "2") (pinfunction "2_2") (pintype "passive"))
    )
    (net (code "66") (name "Net-(U1A-VCAP_1)") (class "Default")
      (node (ref "C6") (pin "2") (pinfunction "2_2") (pintype "passive"))
      (node (ref "U1") (pin "31") (pinfunction "VCAP_1_31") (pintype "passive"))
    )
    (net (code "67") (name "Net-(U1A-VCAP_2)") (class "Default")
      (node (ref "C5") (pin "2") (pinfunction "2_2") (pintype "passive"))
      (node (ref "U1") (pin "47") (pinfunction "VCAP_2_47") (pintype "passive"))
    )
    (net (code "68") (name "Net-(USB-CC1)") (class "Default")
      (node (ref "R10") (pin "1") (pinfunction "1_1") (pintype "passive"))
      (node (ref "USB") (pin "A5") (pinfunction "CC1_A5") (pintype "passive"))
    )
    (net (code "69") (name "Net-(USB-CC2)") (class "Default")
      (node (ref "R12") (pin "1") (pinfunction "1_1") (pintype "passive"))
      (node (ref "USB") (pin "B5") (pinfunction "CC2_B5") (pintype "passive"))
    )
    (net (code "70") (name "VBAT") (class "Default")
      (node (ref "C3") (pin "1") (pinfunction "1_1") (pintype "passive"))
      (node (ref "D1") (pin "3") (pinfunction "K_3") (pintype "passive"))
      (node (ref "U1") (pin "1") (pinfunction "VBAT_1") (pintype "passive"))
    )
    (net (code "71") (name "VBUS") (class "Default")
      (node (ref "C18") (pin "2") (pinfunction "2_2") (pintype "passive"))
      (node (ref "SBC") (pin "2") (pinfunction "2_2") (pintype "passive"))
      (node (ref "U2") (pin "2") (pinfunction "VIN_2") (pintype "passive"))
      (node (ref "USB") (pin "A4") (pinfunction "VBUS_A4") (pintype "passive"))
      (node (ref "USB") (pin "A9") (pinfunction "VBUS_A9") (pintype "passive"))
      (node (ref "USB") (pin "B4") (pinfunction "VBUS_B4") (pintype "passive"))
      (node (ref "USB") (pin "B9") (pinfunction "VBUS_B9") (pintype "passive"))
    )
    (net (code "72") (name "VCC") (class "Default")
      (node (ref "C17") (pin "1") (pinfunction "1_1") (pintype "passive"))
      (node (ref "J2") (pin "27") (pinfunction "27_27") (pintype "passive"))
      (node (ref "J2") (pin "28") (pinfunction "28_28") (pintype "passive"))
      (node (ref "SBC") (pin "1") (pinfunction "1_1") (pintype "passive"))
      (node (ref "U2") (pin "3") (pinfunction "VOUT_3") (pintype "passive"))
      (node (ref "U3") (pin "2") (pinfunction "VIN_2") (pintype "passive"))
    )
    (net (code "73") (name "VDD33") (class "Default")
      (node (ref "BOOT") (pin "2") (pinfunction "NO_2") (pintype "passive"))
      (node (ref "C11") (pin "2") (pinfunction "2_2") (pintype "passive"))
      (node (ref "C12") (pin "2") (pinfunction "2_2") (pintype "passive"))
      (node (ref "C13") (pin "2") (pinfunction "2_2") (pintype "passive"))
      (node (ref "C16") (pin "2") (pinfunction "2_2") (pintype "passive"))
      (node (ref "C19") (pin "2") (pinfunction "2_2") (pintype "passive"))
      (node (ref "C20") (pin "2") (pinfunction "2_2") (pintype "passive"))
      (node (ref "C21") (pin "2") (pinfunction "2_2") (pintype "passive"))
      (node (ref "CARD1") (pin "4") (pinfunction "VDD_4") (pintype "passive"))
      (node (ref "D1") (pin "1") (pinfunction "A1_1") (pintype "passive"))
      (node (ref "J1") (pin "25") (pinfunction "25_25") (pintype "passive"))
      (node (ref "J1") (pin "27") (pinfunction "27_27") (pintype "passive"))
      (node (ref "J1") (pin "29") (pinfunction "29_29") (pintype "passive"))
      (node (ref "L1") (pin "1") (pinfunction "1_1") (pintype "passive"))
      (node (ref "P1") (pin "1") (pinfunction "1_1") (pintype "passive"))
      (node (ref "PC13") (pin "2") (pinfunction "NO_2") (pintype "passive"))
      (node (ref "R1") (pin "2") (pinfunction "2_2") (pintype "passive"))
      (node (ref "R6") (pin "1") (pinfunction "1_1") (pintype "passive"))
      (node (ref "R9") (pin "2") (pinfunction "2_2") (pintype "passive"))
      (node (ref "U1") (pin "19") (pinfunction "VDD_19") (pintype "passive"))
      (node (ref "U1") (pin "32") (pinfunction "VDD_32") (pintype "passive"))
      (node (ref "U1") (pin "48") (pinfunction "VDD_48") (pintype "passive"))
      (node (ref "U1") (pin "64") (pinfunction "VDD_64") (pintype "passive"))
      (node (ref "U3") (pin "3") (pinfunction "VOUT_3") (pintype "passive"))
    )
    (net (code "74") (name "VDD33A") (class "Default")
      (node (ref "C8") (pin "2") (pinfunction "2_2") (pintype "passive"))
      (node (ref "C9") (pin "2") (pinfunction "2_2") (pintype "passive"))
      (node (ref "L1") (pin "2") (pinfunction "2_2") (pintype "passive"))
      (node (ref "U1") (pin "13") (pinfunction "VDDA_13") (pintype "passive"))
    )
    (net (code "75") (name "unconnected-(USB-SBU1-PadA8)") (class "Default")
      (node (ref "USB") (pin "A8") (pinfunction "SBU1_A8") (pintype "passive+no_connect"))
    )
    (net (code "76") (name "unconnected-(USB-SBU2-PadB8)") (class "Default")
      (node (ref "USB") (pin "B8") (pinfunction "SBU2_B8") (pintype "passive+no_connect"))
    )
  )
)
